# ddrive-esp-deadrail-1-8-routed.net
KiCad netlist of a schematic drawn in EAGLE
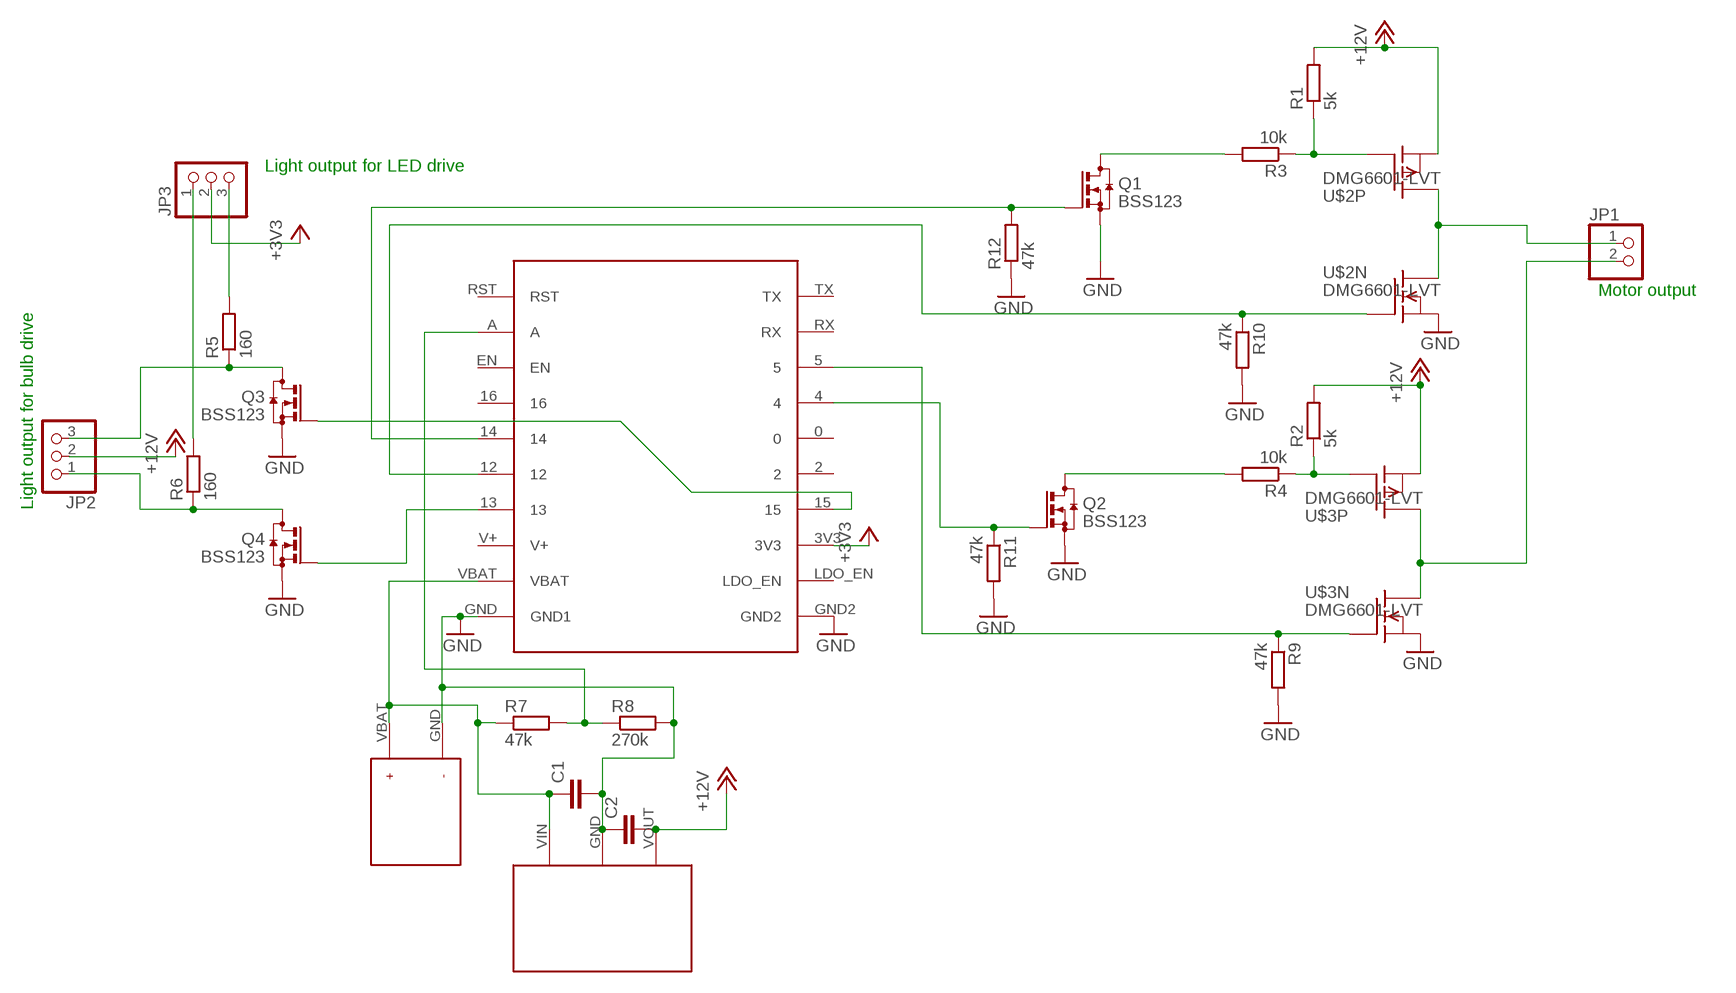
[diagram p0: schematic, sheet 1]

(export (version "E")
  (design (tool "Eeschema 10.0.6"))
  (components
    (comp (ref "C1")
      (value "C-EUC1210")
      (footprint "eagle-import:C1210")
      (libsource (lib "eagle-import") (part "C-EUC1210"))
    )
    (comp (ref "C2")
      (value "C-EUC1210")
      (footprint "eagle-import:C1210")
      (libsource (lib "eagle-import") (part "C-EUC1210"))
    )
    (comp (ref "JP1")
      (value "PINHD-1X2")
      (footprint "eagle-import:1X02")
      (libsource (lib "eagle-import") (part "PINHD-1X2"))
    )
    (comp (ref "JP2")
      (value "PINHD-1X3")
      (footprint "eagle-import:1X03")
      (libsource (lib "eagle-import") (part "PINHD-1X3"))
    )
    (comp (ref "JP3")
      (value "PINHD-1X3")
      (footprint "eagle-import:1X03")
      (libsource (lib "eagle-import") (part "PINHD-1X3"))
    )
    (comp (ref "Q1")
      (value "BSS123")
      (footprint "eagle-import:SOT23")
      (libsource (lib "eagle-import") (part "BSS123"))
    )
    (comp (ref "Q2")
      (value "BSS123")
      (footprint "eagle-import:SOT23")
      (libsource (lib "eagle-import") (part "BSS123"))
    )
    (comp (ref "Q3")
      (value "BSS123")
      (footprint "eagle-import:SOT23")
      (libsource (lib "eagle-import") (part "BSS123"))
    )
    (comp (ref "Q4")
      (value "BSS123")
      (footprint "eagle-import:SOT23")
      (libsource (lib "eagle-import") (part "BSS123"))
    )
    (comp (ref "R1")
      (value "5k")
      (footprint "eagle-import:R0805")
      (libsource (lib "eagle-import") (part "R-EU_R0805"))
    )
    (comp (ref "R2")
      (value "5k")
      (footprint "eagle-import:R0805")
      (libsource (lib "eagle-import") (part "R-EU_R0805"))
    )
    (comp (ref "R3")
      (value "10k")
      (footprint "eagle-import:R0805")
      (libsource (lib "eagle-import") (part "R-EU_R0805"))
    )
    (comp (ref "R4")
      (value "10k")
      (footprint "eagle-import:R0805")
      (libsource (lib "eagle-import") (part "R-EU_R0805"))
    )
    (comp (ref "R5")
      (value "160")
      (footprint "eagle-import:R0805")
      (libsource (lib "eagle-import") (part "R-EU_R0805"))
    )
    (comp (ref "R6")
      (value "160")
      (footprint "eagle-import:R0805")
      (libsource (lib "eagle-import") (part "R-EU_R0805"))
    )
    (comp (ref "R7")
      (value "47k")
      (footprint "eagle-import:R0805")
      (libsource (lib "eagle-import") (part "R-EU_R0805"))
    )
    (comp (ref "R8")
      (value "270k")
      (footprint "eagle-import:R0805")
      (libsource (lib "eagle-import") (part "R-EU_R0805"))
    )
    (comp (ref "R9")
      (value "47k")
      (footprint "eagle-import:R0805")
      (libsource (lib "eagle-import") (part "R-EU_R0805"))
    )
    (comp (ref "R10")
      (value "47k")
      (footprint "eagle-import:R0805")
      (libsource (lib "eagle-import") (part "R-EU_R0805"))
    )
    (comp (ref "R11")
      (value "47k")
      (footprint "eagle-import:R0805")
      (libsource (lib "eagle-import") (part "R-EU_R0805"))
    )
    (comp (ref "R12")
      (value "47k")
      (footprint "eagle-import:R0805")
      (libsource (lib "eagle-import") (part "R-EU_R0805"))
    )
    (comp (ref "U$1")
      (value "ESP12-HUZZAH")
      (footprint "eagle-import:ESP12-HUZZAH")
      (libsource (lib "eagle-import") (part "ESP12-HUZZAH"))
    )
    (comp (ref "U$2")
      (value "DMG6601-LVT")
      (footprint "eagle-import:TSOT-26")
      (libsource (lib "eagle-import") (part "DMG6601-LVT"))
    )
    (comp (ref "U$3")
      (value "DMG6601-LVT")
      (footprint "eagle-import:TSOT-26")
      (libsource (lib "eagle-import") (part "DMG6601-LVT"))
    )
    (comp (ref "U$4")
      (value "JST-PINHD")
      (footprint "eagle-import:JST-PINHDR")
      (libsource (lib "eagle-import") (part "JST-PINHD"))
    )
    (comp (ref "U$5")
      (value "POLOLU-VREG12")
      (footprint "eagle-import:POLOLU-REGULATOR")
      (libsource (lib "eagle-import") (part "POLOLU-VREG12"))
    )
  )
  (nets
    (net (code "1") (name "+3V3") (class "Default")
      (node (ref "JP3") (pin "2") (pinfunction "2_2") (pintype "passive"))
      (node (ref "U$1") (pin "3V3") (pinfunction "3V3_3V3") (pintype "power_in"))
    )
    (net (code "2") (name "+12V") (class "Default")
      (node (ref "C2") (pin "2") (pinfunction "2_2") (pintype "passive"))
      (node (ref "JP2") (pin "2") (pinfunction "2_2") (pintype "passive"))
      (node (ref "R1") (pin "2") (pinfunction "2_2") (pintype "passive"))
      (node (ref "R2") (pin "2") (pinfunction "2_2") (pintype "passive"))
      (node (ref "U$2") (pin "2") (pinfunction "S_2") (pintype "passive"))
      (node (ref "U$3") (pin "2") (pinfunction "S_2") (pintype "passive"))
      (node (ref "U$5") (pin "VOUT") (pinfunction "VOUT_VOUT") (pintype "bidirectional"))
    )
    (net (code "3") (name "/V+") (class "Default")
      (node (ref "U$1") (pin "V+") (pinfunction "V+_V+") (pintype "power_in"))
    )
    (net (code "4") (name "GND") (class "Default")
      (node (ref "C1") (pin "2") (pinfunction "2_2") (pintype "passive"))
      (node (ref "C2") (pin "1") (pinfunction "1_1") (pintype "passive"))
      (node (ref "Q1") (pin "2") (pinfunction "S_2") (pintype "passive"))
      (node (ref "Q2") (pin "2") (pinfunction "S_2") (pintype "passive"))
      (node (ref "Q3") (pin "2") (pinfunction "S_2") (pintype "passive"))
      (node (ref "Q4") (pin "2") (pinfunction "S_2") (pintype "passive"))
      (node (ref "R10") (pin "2") (pinfunction "2_2") (pintype "passive"))
      (node (ref "R11") (pin "2") (pinfunction "2_2") (pintype "passive"))
      (node (ref "R12") (pin "1") (pinfunction "1_1") (pintype "passive"))
      (node (ref "R8") (pin "2") (pinfunction "2_2") (pintype "passive"))
      (node (ref "R9") (pin "2") (pinfunction "2_2") (pintype "passive"))
      (node (ref "U$1") (pin "GND") (pinfunction "GND1_GND") (pintype "power_in"))
      (node (ref "U$1") (pin "GND2") (pinfunction "GND2_GND2") (pintype "power_in"))
      (node (ref "U$2") (pin "5") (pinfunction "S_5") (pintype "passive"))
      (node (ref "U$3") (pin "5") (pinfunction "S_5") (pintype "passive"))
      (node (ref "U$4") (pin "GND") (pinfunction "P$1_GND") (pintype "power_in"))
      (node (ref "U$5") (pin "GND") (pinfunction "GND_GND") (pintype "bidirectional"))
    )
    (net (code "5") (name "Net-(JP3-Pad1)") (class "Default")
      (node (ref "JP3") (pin "1") (pinfunction "1_1") (pintype "passive"))
      (node (ref "R6") (pin "2") (pinfunction "2_2") (pintype "passive"))
    )
    (net (code "6") (name "Net-(JP3-Pad3)") (class "Default")
      (node (ref "JP3") (pin "3") (pinfunction "3_3") (pintype "passive"))
      (node (ref "R5") (pin "2") (pinfunction "2_2") (pintype "passive"))
    )
    (net (code "7") (name "Net-(Q1-D)") (class "Default")
      (node (ref "Q1") (pin "3") (pinfunction "D_3") (pintype "passive"))
      (node (ref "R3") (pin "2") (pinfunction "2_2") (pintype "passive"))
    )
    (net (code "8") (name "Net-(Q1-G)") (class "Default")
      (node (ref "Q1") (pin "1") (pinfunction "G_1") (pintype "passive"))
      (node (ref "R12") (pin "2") (pinfunction "2_2") (pintype "passive"))
      (node (ref "U$1") (pin "14") (pinfunction "14_14") (pintype "bidirectional"))
    )
    (net (code "9") (name "Net-(Q2-D)") (class "Default")
      (node (ref "Q2") (pin "3") (pinfunction "D_3") (pintype "passive"))
      (node (ref "R4") (pin "2") (pinfunction "2_2") (pintype "passive"))
    )
    (net (code "10") (name "Net-(Q2-G)") (class "Default")
      (node (ref "Q2") (pin "1") (pinfunction "G_1") (pintype "passive"))
      (node (ref "R11") (pin "1") (pinfunction "1_1") (pintype "passive"))
      (node (ref "U$1") (pin "4") (pinfunction "4_4") (pintype "bidirectional"))
    )
    (net (code "11") (name "Net-(Q3-D)") (class "Default")
      (node (ref "JP2") (pin "3") (pinfunction "3_3") (pintype "passive"))
      (node (ref "Q3") (pin "3") (pinfunction "D_3") (pintype "passive"))
      (node (ref "R5") (pin "1") (pinfunction "1_1") (pintype "passive"))
    )
    (net (code "12") (name "Net-(Q3-G)") (class "Default")
      (node (ref "Q3") (pin "1") (pinfunction "G_1") (pintype "passive"))
      (node (ref "U$1") (pin "15") (pinfunction "15_15") (pintype "bidirectional"))
    )
    (net (code "13") (name "Net-(Q4-D)") (class "Default")
      (node (ref "JP2") (pin "1") (pinfunction "1_1") (pintype "passive"))
      (node (ref "Q4") (pin "3") (pinfunction "D_3") (pintype "passive"))
      (node (ref "R6") (pin "1") (pinfunction "1_1") (pintype "passive"))
    )
    (net (code "14") (name "Net-(Q4-G)") (class "Default")
      (node (ref "Q4") (pin "1") (pinfunction "G_1") (pintype "passive"))
      (node (ref "U$1") (pin "13") (pinfunction "13_13") (pintype "bidirectional"))
    )
    (net (code "15") (name "Net-(R7-Pad2)") (class "Default")
      (node (ref "R7") (pin "2") (pinfunction "2_2") (pintype "passive"))
      (node (ref "R8") (pin "1") (pinfunction "1_1") (pintype "passive"))
      (node (ref "U$1") (pin "A") (pinfunction "A_A") (pintype "bidirectional"))
    )
    (net (code "16") (name "Net-(U$2A-D)") (class "Default")
      (node (ref "JP1") (pin "1") (pinfunction "1_1") (pintype "passive"))
      (node (ref "U$2") (pin "4") (pinfunction "D_4") (pintype "passive"))
      (node (ref "U$2") (pin "6") (pinfunction "D_6") (pintype "passive"))
    )
    (net (code "17") (name "Net-(U$2A-G)") (class "Default")
      (node (ref "R10") (pin "1") (pinfunction "1_1") (pintype "passive"))
      (node (ref "U$1") (pin "12") (pinfunction "12_12") (pintype "bidirectional"))
      (node (ref "U$2") (pin "1") (pinfunction "G_1") (pintype "passive"))
    )
    (net (code "18") (name "Net-(U$2B-G)") (class "Default")
      (node (ref "R1") (pin "1") (pinfunction "1_1") (pintype "passive"))
      (node (ref "R3") (pin "1") (pinfunction "1_1") (pintype "passive"))
      (node (ref "U$2") (pin "3") (pinfunction "G_3") (pintype "passive"))
    )
    (net (code "19") (name "Net-(U$3A-D)") (class "Default")
      (node (ref "JP1") (pin "2") (pinfunction "2_2") (pintype "passive"))
      (node (ref "U$3") (pin "4") (pinfunction "D_4") (pintype "passive"))
      (node (ref "U$3") (pin "6") (pinfunction "D_6") (pintype "passive"))
    )
    (net (code "20") (name "Net-(U$3A-G)") (class "Default")
      (node (ref "R9") (pin "1") (pinfunction "1_1") (pintype "passive"))
      (node (ref "U$1") (pin "5") (pinfunction "5_5") (pintype "bidirectional"))
      (node (ref "U$3") (pin "1") (pinfunction "G_1") (pintype "passive"))
    )
    (net (code "21") (name "Net-(U$3B-G)") (class "Default")
      (node (ref "R2") (pin "1") (pinfunction "1_1") (pintype "passive"))
      (node (ref "R4") (pin "1") (pinfunction "1_1") (pintype "passive"))
      (node (ref "U$3") (pin "3") (pinfunction "G_3") (pintype "passive"))
    )
    (net (code "22") (name "Net-(U$4-P$2)") (class "Default")
      (node (ref "C1") (pin "1") (pinfunction "1_1") (pintype "passive"))
      (node (ref "R7") (pin "1") (pinfunction "1_1") (pintype "passive"))
      (node (ref "U$1") (pin "VBAT") (pinfunction "VBAT_VBAT") (pintype "power_in"))
      (node (ref "U$4") (pin "VBAT") (pinfunction "P$2_VBAT") (pintype "power_in"))
      (node (ref "U$5") (pin "VIN") (pinfunction "VIN_VIN") (pintype "bidirectional"))
    )
    (net (code "23") (name "unconnected-(U$1-Pad0)") (class "Default")
      (node (ref "U$1") (pin "0") (pinfunction "0_0") (pintype "bidirectional"))
    )
    (net (code "24") (name "unconnected-(U$1-Pad2)") (class "Default")
      (node (ref "U$1") (pin "2") (pinfunction "2_2") (pintype "bidirectional"))
    )
    (net (code "25") (name "unconnected-(U$1-Pad16)") (class "Default")
      (node (ref "U$1") (pin "16") (pinfunction "16_16") (pintype "bidirectional"))
    )
    (net (code "26") (name "unconnected-(U$1-PadEN)") (class "Default")
      (node (ref "U$1") (pin "EN") (pinfunction "EN_EN") (pintype "bidirectional"))
    )
    (net (code "27") (name "unconnected-(U$1-PadLDO_EN)") (class "Default")
      (node (ref "U$1") (pin "LDO_EN") (pinfunction "LDO_EN_LDO_EN") (pintype "bidirectional"))
    )
    (net (code "28") (name "unconnected-(U$1-PadRST)") (class "Default")
      (node (ref "U$1") (pin "RST") (pinfunction "RST_RST") (pintype "bidirectional"))
    )
    (net (code "29") (name "unconnected-(U$1-PadRX)") (class "Default")
      (node (ref "U$1") (pin "RX") (pinfunction "RX_RX") (pintype "bidirectional"))
    )
    (net (code "30") (name "unconnected-(U$1-PadTX)") (class "Default")
      (node (ref "U$1") (pin "TX") (pinfunction "TX_TX") (pintype "bidirectional"))
    )
  )
)
